# current_amplification.net
KiCad netlist of a schematic drawn in Altium Designer
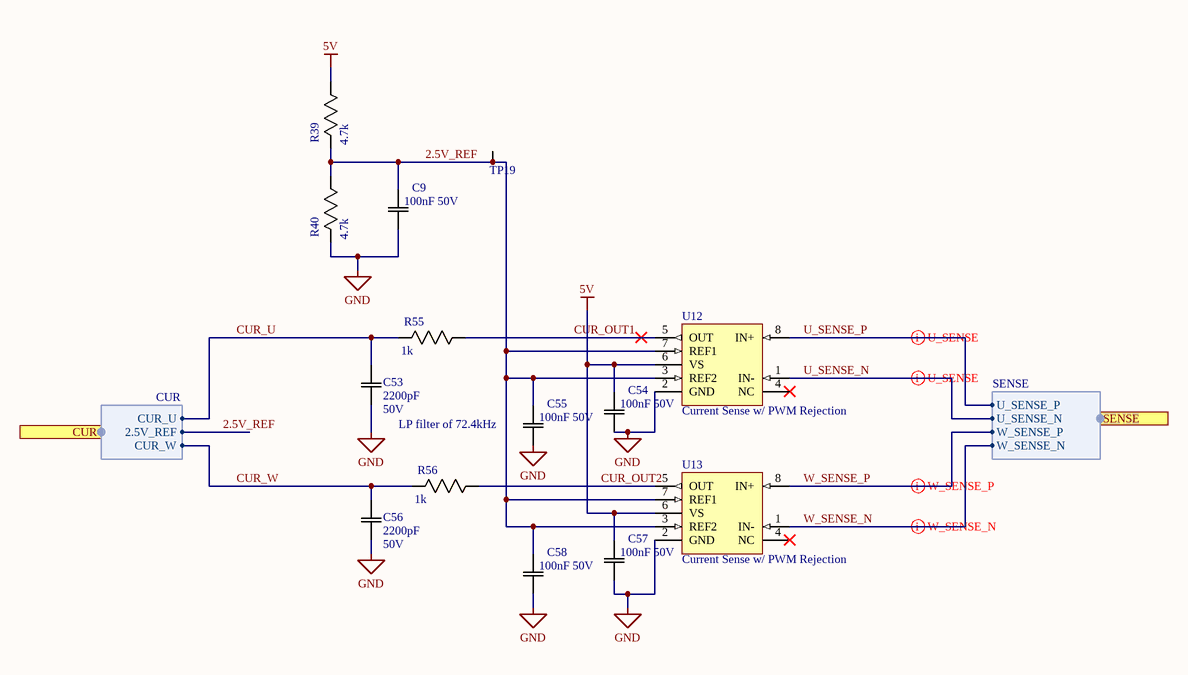
[diagram p0: current_amplification.SchDoc]

(export (version "E")
  (design (tool "Eeschema 10.0.6"))
  (components
    (comp (ref "C9")
      (value "100nF 50V")
      (footprint "0603")
      (description "Default Symbol for Capacitors")
      (fields (field (name "TOLERANCE") "10%") (field (name "PART NUMBER") "CAP 100nF 50V"))
      (libsource (lib "capacitor_library") (part "CAP_Default"))
    )
    (comp (ref "C53")
      (value "2200pF")
      (footprint "0603")
      (description "Default Symbol for Capacitors")
      (fields
        (field (name "TOLERANCE") "10%")
        (field (name "RATING") "50V")
        (field (name "PART NUMBER") "CAP 2200pF 50V")
      )
      (libsource (lib "capacitor_library") (part "CAP_Default"))
    )
    (comp (ref "C54")
      (value "100nF 50V")
      (footprint "0603")
      (description "Default Symbol for Capacitors")
      (fields (field (name "TOLERANCE") "10%") (field (name "PART NUMBER") "CAP 100nF 50V"))
      (libsource (lib "capacitor_library") (part "CAP_Default"))
    )
    (comp (ref "C55")
      (value "100nF 50V")
      (footprint "0603")
      (description "Default Symbol for Capacitors")
      (fields (field (name "TOLERANCE") "10%") (field (name "PART NUMBER") "CAP 100nF 50V"))
      (libsource (lib "capacitor_library") (part "CAP_Default"))
    )
    (comp (ref "C56")
      (value "2200pF")
      (footprint "0603")
      (description "Default Symbol for Capacitors")
      (fields
        (field (name "TOLERANCE") "10%")
        (field (name "RATING") "50V")
        (field (name "PART NUMBER") "CAP 2200pF 50V")
      )
      (libsource (lib "capacitor_library") (part "CAP_Default"))
    )
    (comp (ref "C57")
      (value "100nF 50V")
      (footprint "0603")
      (description "Default Symbol for Capacitors")
      (fields (field (name "TOLERANCE") "10%") (field (name "PART NUMBER") "CAP 100nF 50V"))
      (libsource (lib "capacitor_library") (part "CAP_Default"))
    )
    (comp (ref "C58")
      (value "100nF 50V")
      (footprint "0603")
      (description "Default Symbol for Capacitors")
      (fields (field (name "TOLERANCE") "10%") (field (name "PART NUMBER") "CAP 100nF 50V"))
      (libsource (lib "capacitor_library") (part "CAP_Default"))
    )
    (comp (ref "R39")
      (value "4.7k")
      (footprint "0603")
      (description "Default Resistor Symbol")
      (fields (field (name "TOLERANCE") "1%") (field (name "PART NUMBER") "RES 4.7k 1/8W - 1%"))
      (libsource (lib "Resistor_Library") (part "RES_DEFAULT"))
    )
    (comp (ref "R40")
      (value "4.7k")
      (footprint "0603")
      (description "Default Resistor Symbol")
      (fields (field (name "TOLERANCE") "1%") (field (name "PART NUMBER") "RES 4.7k 1/8W - 1%"))
      (libsource (lib "") (part "RES_DEFAULT_1"))
    )
    (comp (ref "R55")
      (value "1k")
      (footprint "0603")
      (description "Default Resistor Symbol")
      (fields (field (name "TOLERANCE") "1%") (field (name "PART NUMBER") "RES 1k 1/8W - 1%"))
      (libsource (lib "Resistor_Library") (part "RES_DEFAULT"))
    )
    (comp (ref "R56")
      (value "1k")
      (footprint "0603")
      (description "Default Resistor Symbol")
      (fields (field (name "TOLERANCE") "1%") (field (name "PART NUMBER") "RES 1k 1/8W - 1%"))
      (libsource (lib "Resistor_Library") (part "RES_DEFAULT"))
    )
    (comp (ref "TP19")
      (value "2.5V")
      (footprint "TP")
      (fields (field (name "PART NUMBER") "Test Point (Via)"))
      (libsource (lib "IC_Library") (part "Test Point (Via)"))
    )
    (comp (ref "U12")
      (value "Current Sense w/ PWM Rejection")
      (footprint "8-SOIC")
      (description "SP Amp Current Sense Amp Single R-R O/P 5.5V Automotive 6-Pin SC-70 T/R")
      (fields (field (name "PART NUMBER") "INA240A3EDRQ1"))
      (libsource (lib "IC_Library") (part "INA240A3EDRQ1"))
    )
    (comp (ref "U13")
      (value "Current Sense w/ PWM Rejection")
      (footprint "8-SOIC")
      (description "SP Amp Current Sense Amp Single R-R O/P 5.5V Automotive 6-Pin SC-70 T/R")
      (fields (field (name "PART NUMBER") "INA240A3EDRQ1"))
      (libsource (lib "IC_Library") (part "INA240A3EDRQ1"))
    )
  )
  (nets
    (net (code "3") (name "/2.5V_REF") (class "Default")
      (node (ref "C55") (pin "2") (pinfunction "C2_2") (pintype "passive"))
      (node (ref "C58") (pin "2") (pinfunction "C2_2") (pintype "passive"))
      (node (ref "C9") (pin "2") (pinfunction "C2_2") (pintype "passive"))
      (node (ref "R39") (pin "2") (pinfunction "R2_2") (pintype "passive"))
      (node (ref "R40") (pin "1") (pinfunction "R1_1") (pintype "passive"))
      (node (ref "TP19") (pin "1") (pinfunction "1_1") (pintype "passive"))
      (node (ref "U12") (pin "3") (pinfunction "REF2_3") (pintype "input"))
      (node (ref "U12") (pin "7") (pinfunction "REF1_7") (pintype "input"))
      (node (ref "U13") (pin "3") (pinfunction "REF2_3") (pintype "input"))
      (node (ref "U13") (pin "7") (pinfunction "REF1_7") (pintype "input"))
    )
    (net (code "4") (name "/CUR_OUT1") (class "Default")
      (node (ref "R55") (pin "1") (pinfunction "R1_1") (pintype "passive"))
      (node (ref "U12") (pin "5") (pinfunction "OUT_5") (pintype "output"))
    )
    (net (code "5") (name "/CUR_OUT2") (class "Default")
      (node (ref "R56") (pin "1") (pinfunction "R1_1") (pintype "passive"))
      (node (ref "U13") (pin "5") (pinfunction "OUT_5") (pintype "output"))
    )
    (net (code "6") (name "/CUR_U") (class "Default")
      (node (ref "C53") (pin "2") (pinfunction "C2_2") (pintype "passive"))
      (node (ref "R55") (pin "2") (pinfunction "R2_2") (pintype "passive"))
    )
    (net (code "7") (name "/CUR_W") (class "Default")
      (node (ref "C56") (pin "2") (pinfunction "C2_2") (pintype "passive"))
      (node (ref "R56") (pin "2") (pinfunction "R2_2") (pintype "passive"))
    )
    (net (code "8") (name "/U_SENSE_N") (class "Default")
      (node (ref "U12") (pin "1") (pinfunction "IN-_1") (pintype "input"))
    )
    (net (code "9") (name "/U_SENSE_P") (class "Default")
      (node (ref "U12") (pin "8") (pinfunction "IN+_8") (pintype "input"))
    )
    (net (code "10") (name "/W_SENSE_N") (class "Default")
      (node (ref "U13") (pin "1") (pinfunction "IN-_1") (pintype "input"))
    )
    (net (code "11") (name "/W_SENSE_P") (class "Default")
      (node (ref "U13") (pin "8") (pinfunction "IN+_8") (pintype "input"))
    )
    (net (code "14") (name "5V") (class "Default")
      (node (ref "C54") (pin "2") (pinfunction "C2_2") (pintype "passive"))
      (node (ref "C57") (pin "2") (pinfunction "C2_2") (pintype "passive"))
      (node (ref "R39") (pin "1") (pinfunction "R1_1") (pintype "passive"))
      (node (ref "U12") (pin "6") (pinfunction "VS_6") (pintype "power_in"))
      (node (ref "U13") (pin "6") (pinfunction "VS_6") (pintype "power_in"))
    )
    (net (code "15") (name "GND") (class "Default")
      (node (ref "C53") (pin "1") (pinfunction "C1_1") (pintype "passive"))
      (node (ref "C54") (pin "1") (pinfunction "C1_1") (pintype "passive"))
      (node (ref "C55") (pin "1") (pinfunction "C1_1") (pintype "passive"))
      (node (ref "C56") (pin "1") (pinfunction "C1_1") (pintype "passive"))
      (node (ref "C57") (pin "1") (pinfunction "C1_1") (pintype "passive"))
      (node (ref "C58") (pin "1") (pinfunction "C1_1") (pintype "passive"))
      (node (ref "C9") (pin "1") (pinfunction "C1_1") (pintype "passive"))
      (node (ref "R40") (pin "2") (pinfunction "R2_2") (pintype "passive"))
      (node (ref "U12") (pin "2") (pinfunction "GND_2") (pintype "power_in"))
      (node (ref "U13") (pin "2") (pinfunction "GND_2") (pintype "power_in"))
    )
    (net (code "16") (name "unconnected-(U12-NC-Pad4)") (class "Default")
      (node (ref "U12") (pin "4") (pinfunction "NC_4") (pintype "passive+no_connect"))
    )
    (net (code "17") (name "unconnected-(U13-NC-Pad4)") (class "Default")
      (node (ref "U13") (pin "4") (pinfunction "NC_4") (pintype "passive+no_connect"))
    )
  )
)
